# RESPi.net
KiCad netlist of a schematic drawn in EasyEDA Pro
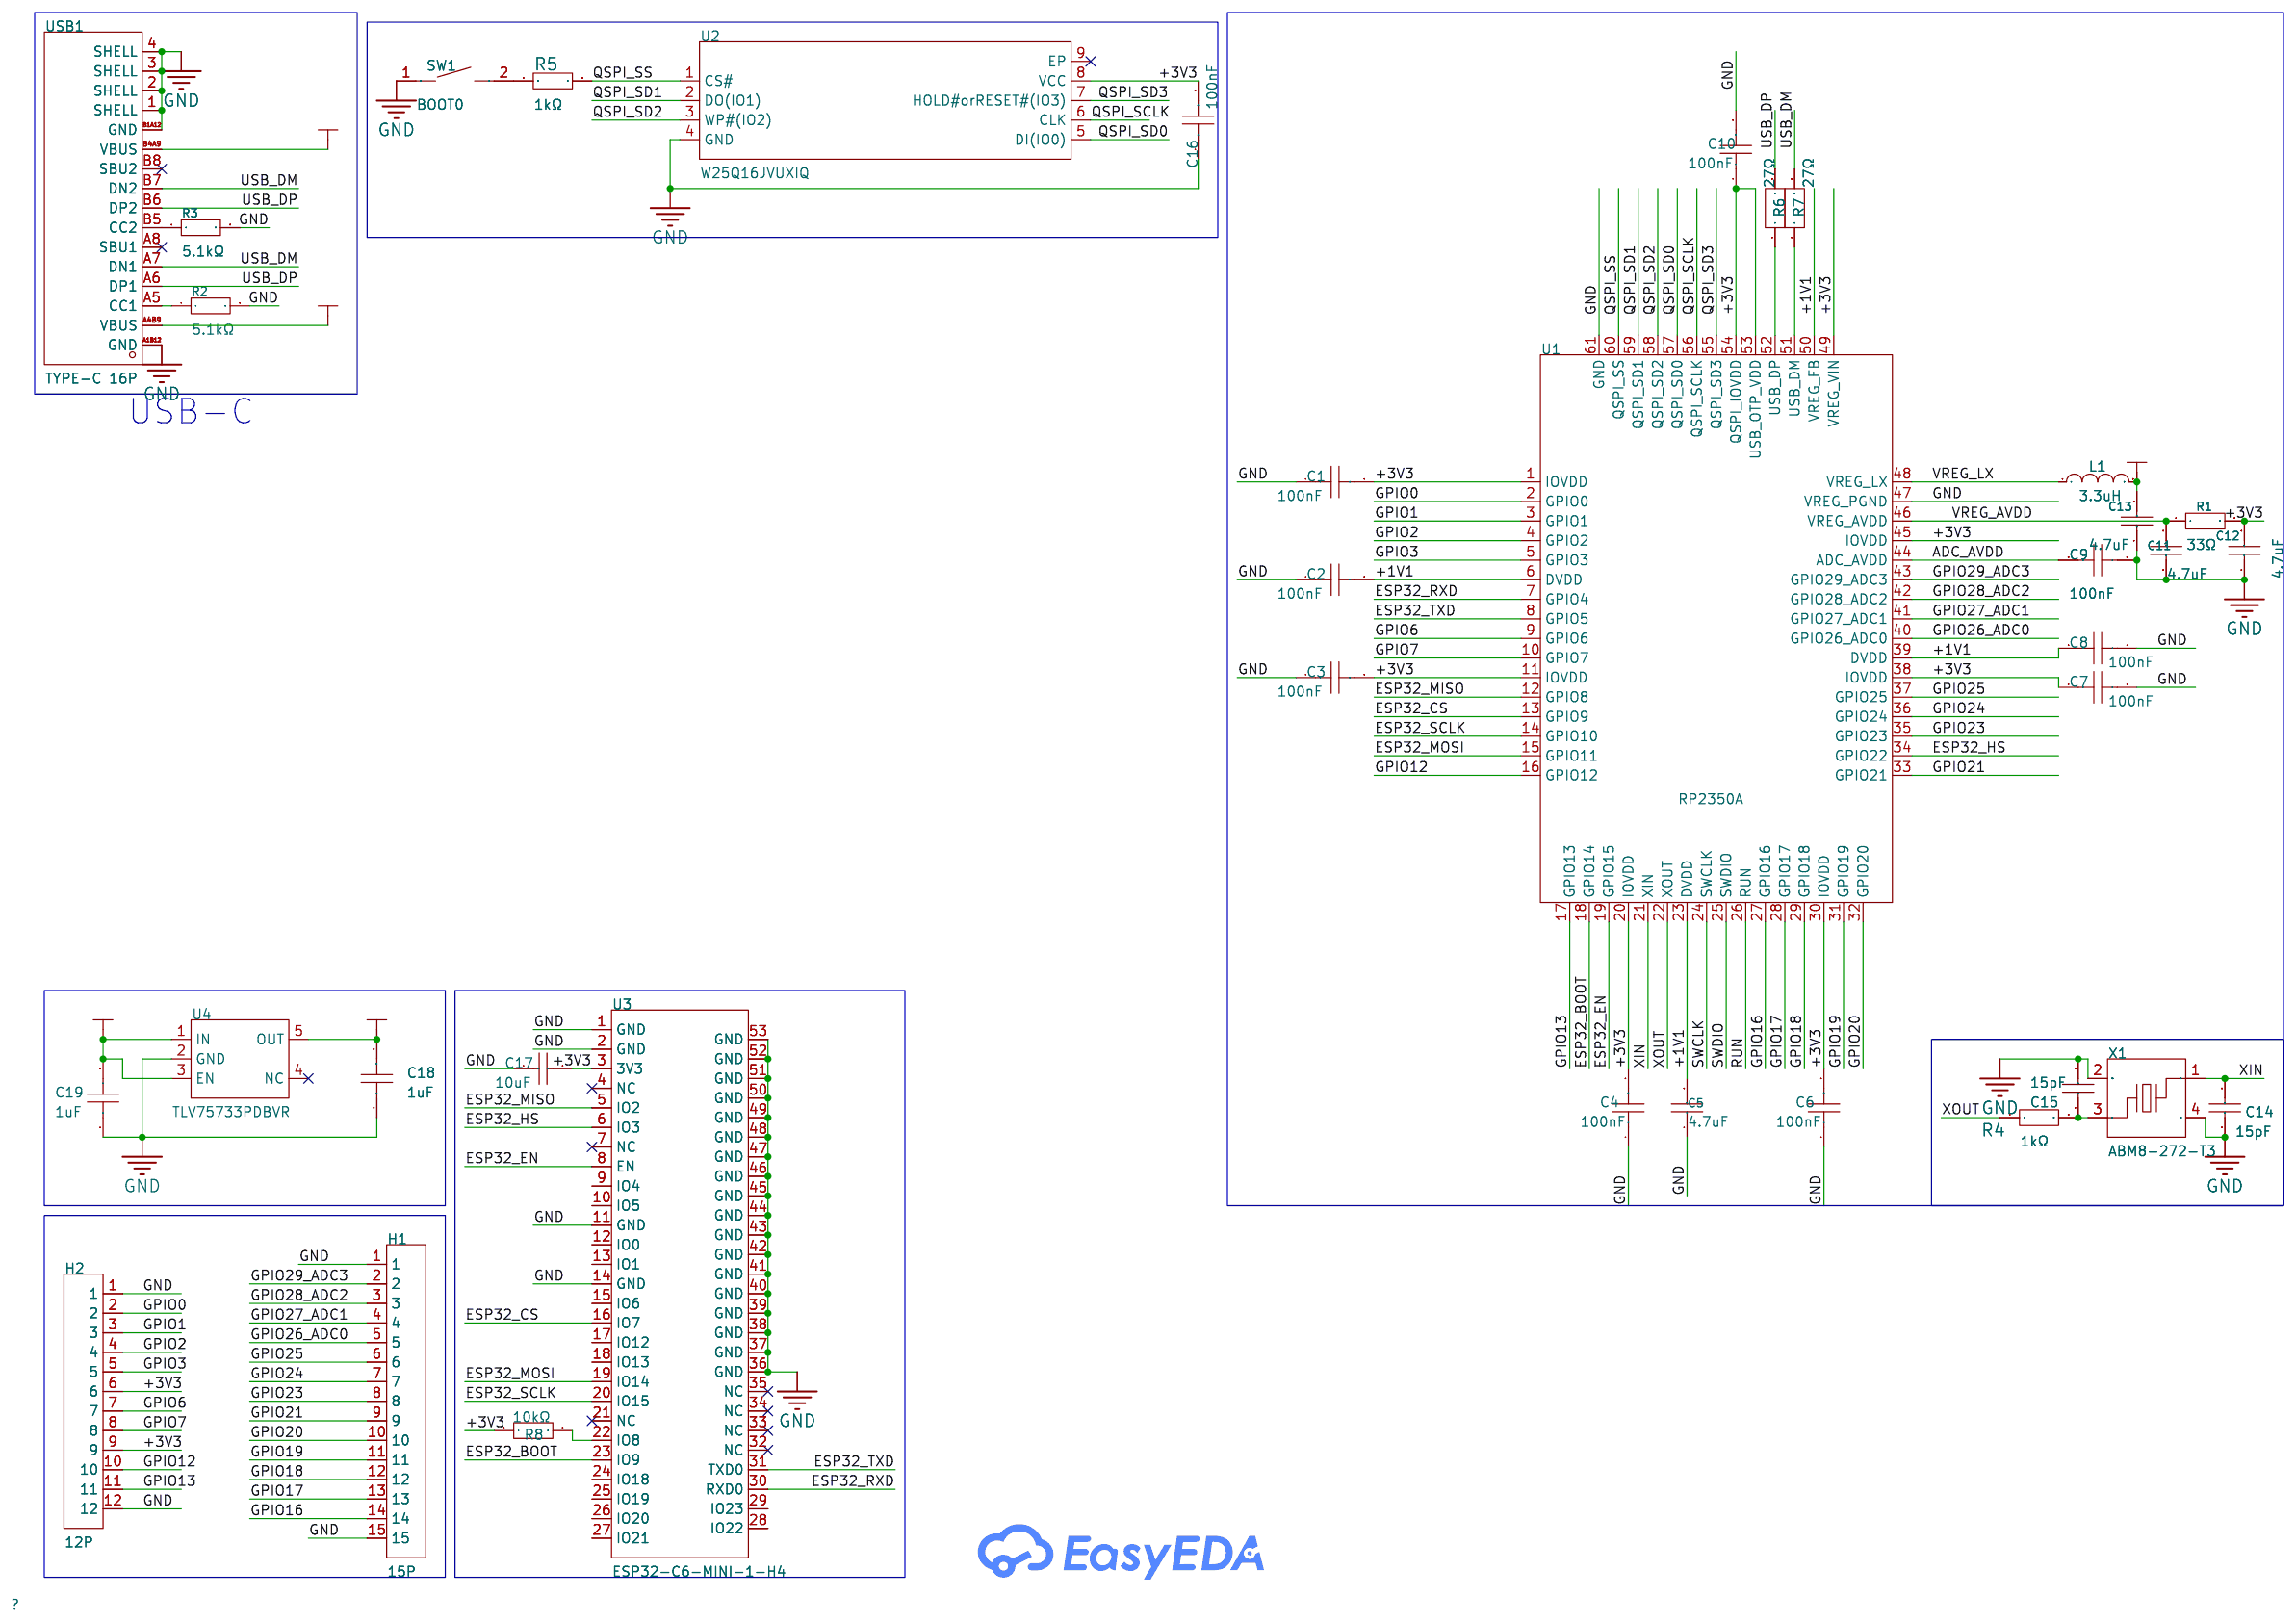
[diagram p0: schematic sheet]

(export (version "E")
  (design (tool "Eeschema 10.0.6"))
  (components
    (comp (ref "C1")
      (value "100nF")
      (footprint "easyedapro:C0402")
      (fields
        (field (name "Manufacturer Part") "CL05B104KO5NNNC")
        (field (name "Manufacturer") "SAMSUNG(三星)")
      )
      (libsource (lib "easyedapro") (part "CL05B104KO5NNNC"))
    )
    (comp (ref "C2")
      (value "100nF")
      (footprint "easyedapro:C0402")
      (fields
        (field (name "Manufacturer Part") "CL05B104KO5NNNC")
        (field (name "Manufacturer") "SAMSUNG(三星)")
      )
      (libsource (lib "easyedapro") (part "CL05B104KO5NNNC"))
    )
    (comp (ref "C3")
      (value "100nF")
      (footprint "easyedapro:C0402")
      (fields
        (field (name "Manufacturer Part") "CL05B104KO5NNNC")
        (field (name "Manufacturer") "SAMSUNG(三星)")
      )
      (libsource (lib "easyedapro") (part "CL05B104KO5NNNC"))
    )
    (comp (ref "C4")
      (value "100nF")
      (footprint "easyedapro:C0402")
      (fields
        (field (name "Manufacturer Part") "CL05B104KO5NNNC")
        (field (name "Manufacturer") "SAMSUNG(三星)")
      )
      (libsource (lib "easyedapro") (part "CL05B104KO5NNNC"))
    )
    (comp (ref "C5")
      (value "4.7uF")
      (footprint "easyedapro:C0402")
      (fields
        (field (name "Manufacturer Part") "CL05A475MP5NRNC")
        (field (name "Manufacturer") "SAMSUNG(三星)")
      )
      (libsource (lib "easyedapro") (part "CL05A475MP5NRNC"))
    )
    (comp (ref "C6")
      (value "100nF")
      (footprint "easyedapro:C0402")
      (fields
        (field (name "Manufacturer Part") "CL05B104KO5NNNC")
        (field (name "Manufacturer") "SAMSUNG(三星)")
      )
      (libsource (lib "easyedapro") (part "CL05B104KO5NNNC"))
    )
    (comp (ref "C7")
      (value "100nF")
      (footprint "easyedapro:C0402")
      (fields
        (field (name "Manufacturer Part") "CL05B104KO5NNNC")
        (field (name "Manufacturer") "SAMSUNG(三星)")
      )
      (libsource (lib "easyedapro") (part "CL05B104KO5NNNC"))
    )
    (comp (ref "C8")
      (value "100nF")
      (footprint "easyedapro:C0402")
      (fields
        (field (name "Manufacturer Part") "CL05B104KO5NNNC")
        (field (name "Manufacturer") "SAMSUNG(三星)")
      )
      (libsource (lib "easyedapro") (part "CL05B104KO5NNNC"))
    )
    (comp (ref "C9")
      (value "100nF")
      (footprint "easyedapro:C0402")
      (fields
        (field (name "Manufacturer Part") "CL05B104KO5NNNC")
        (field (name "Manufacturer") "SAMSUNG(三星)")
      )
      (libsource (lib "easyedapro") (part "CL05B104KO5NNNC"))
    )
    (comp (ref "C10")
      (value "100nF")
      (footprint "easyedapro:C0402")
      (fields
        (field (name "Manufacturer Part") "CL05B104KO5NNNC")
        (field (name "Manufacturer") "SAMSUNG(三星)")
      )
      (libsource (lib "easyedapro") (part "CL05B104KO5NNNC"))
    )
    (comp (ref "C11")
      (value "4.7uF")
      (footprint "easyedapro:C0402")
      (fields
        (field (name "Manufacturer Part") "CL05A475MP5NRNC")
        (field (name "Manufacturer") "SAMSUNG(三星)")
      )
      (libsource (lib "easyedapro") (part "CL05A475MP5NRNC"))
    )
    (comp (ref "C12")
      (value "4.7uF")
      (footprint "easyedapro:C0402")
      (fields
        (field (name "Manufacturer Part") "CL05A475MP5NRNC")
        (field (name "Manufacturer") "SAMSUNG(三星)")
      )
      (libsource (lib "easyedapro") (part "CL05A475MP5NRNC"))
    )
    (comp (ref "C13")
      (value "4.7uF")
      (footprint "easyedapro:C0402")
      (fields
        (field (name "Manufacturer Part") "CL05A475MP5NRNC")
        (field (name "Manufacturer") "SAMSUNG(三星)")
      )
      (libsource (lib "easyedapro") (part "CL05A475MP5NRNC"))
    )
    (comp (ref "C14")
      (value "15pF")
      (footprint "easyedapro:C0402")
      (fields (field (name "Manufacturer Part") "0402CG150J500NT") (field (name "Manufacturer") "FH(风华)"))
      (libsource (lib "easyedapro") (part "0402CG150J500NT"))
    )
    (comp (ref "C15")
      (value "15pF")
      (footprint "easyedapro:C0402")
      (fields (field (name "Manufacturer Part") "0402CG150J500NT") (field (name "Manufacturer") "FH(风华)"))
      (libsource (lib "easyedapro") (part "0402CG150J500NT"))
    )
    (comp (ref "C16")
      (value "100nF")
      (footprint "easyedapro:C0402")
      (fields
        (field (name "Manufacturer Part") "CL05B104KO5NNNC")
        (field (name "Manufacturer") "SAMSUNG(三星)")
      )
      (libsource (lib "easyedapro") (part "CL05B104KO5NNNC"))
    )
    (comp (ref "C17")
      (value "10uF")
      (footprint "easyedapro:C0402")
      (description "Capacitance:10uF Tolerance:±20% Tolerance:±20% Voltage Rating:6.3V Temperature Coefficient:X5R")
      (fields
        (field (name "Manufacturer Part") "CL05A106MQ5NUNC")
        (field (name "Manufacturer") "SAMSUNG(三星)")
      )
      (libsource (lib "easyedapro") (part "CL05A106MQ5NUNC"))
    )
    (comp (ref "C18")
      (value "1uF")
      (footprint "easyedapro:C0402")
      (description "Capacitance:1uF Tolerance:±10% Tolerance:±10% Voltage Rating:25V Temperature Coefficient:X5R")
      (fields
        (field (name "Manufacturer Part") "CL05A105KA5NQNC")
        (field (name "Manufacturer") "SAMSUNG(三星)")
      )
      (libsource (lib "easyedapro") (part "CL05A105KA5NQNC"))
    )
    (comp (ref "C19")
      (value "1uF")
      (footprint "easyedapro:C0402")
      (description "Capacitance:1uF Tolerance:±10% Tolerance:±10% Voltage Rating:25V Temperature Coefficient:X5R")
      (fields
        (field (name "Manufacturer Part") "CL05A105KA5NQNC")
        (field (name "Manufacturer") "SAMSUNG(三星)")
      )
      (libsource (lib "easyedapro") (part "CL05A105KA5NQNC"))
    )
    (comp (ref "H1")
      (value "15P")
      (footprint "easyedapro:HDR-TH_15P-P2.54-V-M")
      (fields (field (name "Manufacturer") "XKB Connection(中国星坤)"))
      (libsource (lib "easyedapro") (part "X6511WV-15H-C30D60"))
    )
    (comp (ref "H2")
      (value "12P")
      (footprint "easyedapro:HDR-TH_12P-P2.54-V-M")
      (fields (field (name "Manufacturer") "XKB Connection(中国星坤)"))
      (libsource (lib "easyedapro") (part "X6511WV-12H-C30D60"))
    )
    (comp (ref "L1")
      (value "3.3uH")
      (footprint "easyedapro:IND-SMD_L2.0-W1.6_AOTA-B201610S3R3-101-T")
      (fields (field (name "Manufacturer") "ABRACON"))
      (libsource (lib "easyedapro") (part "AOTA-B201610S3R3-101-T"))
    )
    (comp (ref "R1")
      (value "33Ω")
      (footprint "easyedapro:R0402")
      (fields
        (field (name "Manufacturer Part") "0402WGF330JTCE")
        (field (name "Manufacturer") "UNI-ROYAL(厚声)")
      )
      (libsource (lib "easyedapro") (part "0402WGF330JTCE"))
    )
    (comp (ref "R2")
      (value "5.1kΩ")
      (footprint "easyedapro:R0402")
      (fields
        (field (name "Manufacturer Part") "0402WGF5101TCE")
        (field (name "Manufacturer") "UNI-ROYAL(厚声)")
      )
      (libsource (lib "easyedapro") (part "0402WGF5101TCE"))
    )
    (comp (ref "R3")
      (value "5.1kΩ")
      (footprint "easyedapro:R0402")
      (fields
        (field (name "Manufacturer Part") "0402WGF5101TCE")
        (field (name "Manufacturer") "UNI-ROYAL(厚声)")
      )
      (libsource (lib "easyedapro") (part "0402WGF5101TCE"))
    )
    (comp (ref "R4")
      (value "1kΩ")
      (footprint "easyedapro:R0402")
      (fields
        (field (name "Manufacturer Part") "0402WGF1001TCE")
        (field (name "Manufacturer") "UNI-ROYAL(厚声)")
      )
      (libsource (lib "easyedapro") (part "0402WGF1001TCE"))
    )
    (comp (ref "R5")
      (value "1kΩ")
      (footprint "easyedapro:R0402")
      (fields
        (field (name "Manufacturer Part") "0402WGF1001TCE")
        (field (name "Manufacturer") "UNI-ROYAL(厚声)")
      )
      (libsource (lib "easyedapro") (part "0402WGF1001TCE"))
    )
    (comp (ref "R6")
      (value "27Ω")
      (footprint "easyedapro:R0402")
      (fields (field (name "Manufacturer Part") "WR04X270JTL") (field (name "Manufacturer") "Walsin(华新科)"))
      (libsource (lib "easyedapro") (part "WR04X270 JTL"))
    )
    (comp (ref "R7")
      (value "27Ω")
      (footprint "easyedapro:R0402")
      (fields (field (name "Manufacturer Part") "WR04X270JTL") (field (name "Manufacturer") "Walsin(华新科)"))
      (libsource (lib "easyedapro") (part "WR04X270 JTL"))
    )
    (comp (ref "R8")
      (value "10kΩ")
      (footprint "easyedapro:R0402")
      (fields
        (field (name "Manufacturer Part") "0402WGF1002TCE")
        (field (name "Manufacturer") "UNI-ROYAL(厚声)")
      )
      (libsource (lib "easyedapro") (part "0402WGF1002TCE"))
    )
    (comp (ref "SW1")
      (value "BOOT0")
      (footprint "easyedapro:SW-SMD_L3.9-W3.0-P4.45")
      (fields (field (name "Manufacturer") "XUNPU(讯普)"))
      (libsource (lib "easyedapro") (part "TS-1088-AR02016"))
    )
    (comp (ref "U1")
      (value "RP2350A")
      (footprint "easyedapro:QFN-60_L7.0-W7.0-P0.40-TL-EP3.4")
      (fields (field (name "Manufacturer") "Raspberry Pi(树莓派)"))
      (libsource (lib "easyedapro") (part "RP2350A_C42411118"))
    )
    (comp (ref "U2")
      (value "W25Q16JVUXIQ")
      (footprint "easyedapro:USON-8_L3.0-W2.0-P0.50-BL-EP")
      (fields (field (name "Manufacturer") "Winbond(华邦)"))
      (libsource (lib "easyedapro") (part "W25Q16JVUXIQ"))
    )
    (comp (ref "U3")
      (value "ESP32-C6-MINI-1-H4")
      (footprint "easyedapro:WIFIM-SMD_61P-L16.6-W13.2-P0.80-ESP32-C6-MINI-1-N4")
      (fields (field (name "Manufacturer") "ESPRESSIF(乐鑫)"))
      (libsource (lib "easyedapro") (part "ESP32-C6-MINI-1-H4"))
    )
    (comp (ref "U4")
      (value "TLV75733PDBVR")
      (footprint "easyedapro:SOT-23-5_L2.9-W1.6-P0.95-LS2.8-BL")
      (fields (field (name "Manufacturer") "TI(德州仪器)"))
      (libsource (lib "easyedapro") (part "TLV75733PDBVR"))
    )
    (comp (ref "USB1")
      (value "TYPE-C 16P")
      (footprint "easyedapro:USB-C-SMD_TYPE-C16PIN")
      (fields (field (name "Manufacturer") "SHOU HAN(首韩)"))
      (libsource (lib "easyedapro") (part "TYPE-C16PIN"))
    )
    (comp (ref "X1")
      (value "ABM8-272-T3")
      (footprint "easyedapro:CRYSTAL-SMD_4P-L3.2-W2.5-BL")
      (fields (field (name "Manufacturer") "ABRACON"))
      (libsource (lib "easyedapro") (part "ABM8-272-T3_C20625731"))
    )
  )
  (nets
    (net (code "1") (name "+1V1") (class "Default")
      (node (ref "C13") (pin "2") (pinfunction "2_2") (pintype "input"))
      (node (ref "C2") (pin "2") (pinfunction "2_2") (pintype "unspecified"))
      (node (ref "C5") (pin "2") (pinfunction "2_2") (pintype "input"))
      (node (ref "C8") (pin "2") (pinfunction "2_2") (pintype "unspecified"))
      (node (ref "L1") (pin "2") (pinfunction "2_2") (pintype "unspecified"))
      (node (ref "U1") (pin "23") (pinfunction "DVDD_23") (pintype "unspecified"))
      (node (ref "U1") (pin "39") (pinfunction "DVDD_39") (pintype "unspecified"))
      (node (ref "U1") (pin "50") (pinfunction "VREG_FB_50") (pintype "unspecified"))
      (node (ref "U1") (pin "6") (pinfunction "DVDD_6") (pintype "unspecified"))
    )
    (net (code "2") (name "+3V3") (class "Default")
      (node (ref "C1") (pin "2") (pinfunction "2_2") (pintype "unspecified"))
      (node (ref "C10") (pin "1") (pinfunction "1_1") (pintype "unspecified"))
      (node (ref "C12") (pin "2") (pinfunction "2_2") (pintype "input"))
      (node (ref "C16") (pin "2") (pinfunction "2_2") (pintype "unspecified"))
      (node (ref "C17") (pin "2") (pinfunction "2_2") (pintype "input"))
      (node (ref "C18") (pin "2") (pinfunction "2_2") (pintype "unspecified"))
      (node (ref "C3") (pin "2") (pinfunction "2_2") (pintype "unspecified"))
      (node (ref "C4") (pin "2") (pinfunction "2_2") (pintype "unspecified"))
      (node (ref "C6") (pin "2") (pinfunction "2_2") (pintype "unspecified"))
      (node (ref "C7") (pin "2") (pinfunction "2_2") (pintype "unspecified"))
      (node (ref "H2") (pin "6") (pinfunction "6_6") (pintype "unspecified"))
      (node (ref "H2") (pin "9") (pinfunction "9_9") (pintype "unspecified"))
      (node (ref "R1") (pin "2") (pinfunction "2_2") (pintype "input"))
      (node (ref "R8") (pin "1") (pinfunction "1_1") (pintype "input"))
      (node (ref "U1") (pin "1") (pinfunction "IOVDD_1") (pintype "unspecified"))
      (node (ref "U1") (pin "11") (pinfunction "IOVDD_11") (pintype "unspecified"))
      (node (ref "U1") (pin "20") (pinfunction "IOVDD_20") (pintype "unspecified"))
      (node (ref "U1") (pin "30") (pinfunction "IOVDD_30") (pintype "unspecified"))
      (node (ref "U1") (pin "38") (pinfunction "IOVDD_38") (pintype "unspecified"))
      (node (ref "U1") (pin "45") (pinfunction "IOVDD_45") (pintype "unspecified"))
      (node (ref "U1") (pin "49") (pinfunction "VREG_VIN_49") (pintype "unspecified"))
      (node (ref "U1") (pin "53") (pinfunction "USB_OTP_VDD_53") (pintype "unspecified"))
      (node (ref "U1") (pin "54") (pinfunction "QSPI_IOVDD_54") (pintype "unspecified"))
      (node (ref "U2") (pin "8") (pinfunction "VCC_8") (pintype "unspecified"))
      (node (ref "U3") (pin "3") (pinfunction "3V3_3") (pintype "unspecified"))
      (node (ref "U4") (pin "5") (pinfunction "OUT_5") (pintype "unspecified"))
    )
    (net (code "3") (name "/ADC_AVDD") (class "Default")
      (node (ref "C9") (pin "2") (pinfunction "2_2") (pintype "unspecified"))
      (node (ref "U1") (pin "44") (pinfunction "ADC_AVDD_44") (pintype "unspecified"))
    )
    (net (code "4") (name "/ESP32_BOOT") (class "Default")
      (node (ref "U1") (pin "18") (pinfunction "GPIO14_18") (pintype "unspecified"))
      (node (ref "U3") (pin "23") (pinfunction "IO9_23") (pintype "unspecified"))
    )
    (net (code "5") (name "/ESP32_CS") (class "Default")
      (node (ref "U1") (pin "13") (pinfunction "GPIO9_13") (pintype "unspecified"))
      (node (ref "U3") (pin "16") (pinfunction "IO7_16") (pintype "unspecified"))
    )
    (net (code "6") (name "/ESP32_EN") (class "Default")
      (node (ref "U1") (pin "19") (pinfunction "GPIO15_19") (pintype "unspecified"))
      (node (ref "U3") (pin "8") (pinfunction "EN_8") (pintype "unspecified"))
    )
    (net (code "7") (name "/ESP32_HS") (class "Default")
      (node (ref "U1") (pin "34") (pinfunction "GPIO22_34") (pintype "unspecified"))
      (node (ref "U3") (pin "6") (pinfunction "IO3_6") (pintype "unspecified"))
    )
    (net (code "8") (name "/ESP32_MISO") (class "Default")
      (node (ref "U1") (pin "12") (pinfunction "GPIO8_12") (pintype "unspecified"))
      (node (ref "U3") (pin "5") (pinfunction "IO2_5") (pintype "unspecified"))
    )
    (net (code "9") (name "/ESP32_MOSI") (class "Default")
      (node (ref "U1") (pin "15") (pinfunction "GPIO11_15") (pintype "unspecified"))
      (node (ref "U3") (pin "19") (pinfunction "IO14_19") (pintype "unspecified"))
    )
    (net (code "10") (name "/ESP32_RXD") (class "Default")
      (node (ref "U1") (pin "7") (pinfunction "GPIO4_7") (pintype "unspecified"))
      (node (ref "U3") (pin "30") (pinfunction "RXD0_30") (pintype "unspecified"))
    )
    (net (code "11") (name "/ESP32_SCLK") (class "Default")
      (node (ref "U1") (pin "14") (pinfunction "GPIO10_14") (pintype "unspecified"))
      (node (ref "U3") (pin "20") (pinfunction "IO15_20") (pintype "unspecified"))
    )
    (net (code "12") (name "/ESP32_TXD") (class "Default")
      (node (ref "U1") (pin "8") (pinfunction "GPIO5_8") (pintype "unspecified"))
      (node (ref "U3") (pin "31") (pinfunction "TXD0_31") (pintype "unspecified"))
    )
    (net (code "13") (name "/GPIO0") (class "Default")
      (node (ref "H2") (pin "2") (pinfunction "2_2") (pintype "unspecified"))
      (node (ref "U1") (pin "2") (pinfunction "GPIO0_2") (pintype "unspecified"))
    )
    (net (code "14") (name "/GPIO1") (class "Default")
      (node (ref "H2") (pin "3") (pinfunction "3_3") (pintype "unspecified"))
      (node (ref "U1") (pin "3") (pinfunction "GPIO1_3") (pintype "unspecified"))
    )
    (net (code "15") (name "/GPIO2") (class "Default")
      (node (ref "H2") (pin "4") (pinfunction "4_4") (pintype "unspecified"))
      (node (ref "U1") (pin "4") (pinfunction "GPIO2_4") (pintype "unspecified"))
    )
    (net (code "16") (name "/GPIO3") (class "Default")
      (node (ref "H2") (pin "5") (pinfunction "5_5") (pintype "unspecified"))
      (node (ref "U1") (pin "5") (pinfunction "GPIO3_5") (pintype "unspecified"))
    )
    (net (code "17") (name "/GPIO6") (class "Default")
      (node (ref "H2") (pin "7") (pinfunction "7_7") (pintype "unspecified"))
      (node (ref "U1") (pin "9") (pinfunction "GPIO6_9") (pintype "unspecified"))
    )
    (net (code "18") (name "/GPIO7") (class "Default")
      (node (ref "H2") (pin "8") (pinfunction "8_8") (pintype "unspecified"))
      (node (ref "U1") (pin "10") (pinfunction "GPIO7_10") (pintype "unspecified"))
    )
    (net (code "19") (name "/GPIO12") (class "Default")
      (node (ref "H2") (pin "10") (pinfunction "10_10") (pintype "unspecified"))
      (node (ref "U1") (pin "16") (pinfunction "GPIO12_16") (pintype "unspecified"))
    )
    (net (code "20") (name "/GPIO13") (class "Default")
      (node (ref "H2") (pin "11") (pinfunction "11_11") (pintype "unspecified"))
      (node (ref "U1") (pin "17") (pinfunction "GPIO13_17") (pintype "unspecified"))
    )
    (net (code "21") (name "/GPIO16") (class "Default")
      (node (ref "H1") (pin "14") (pinfunction "14_14") (pintype "unspecified"))
      (node (ref "U1") (pin "27") (pinfunction "GPIO16_27") (pintype "unspecified"))
    )
    (net (code "22") (name "/GPIO17") (class "Default")
      (node (ref "H1") (pin "13") (pinfunction "13_13") (pintype "unspecified"))
      (node (ref "U1") (pin "28") (pinfunction "GPIO17_28") (pintype "unspecified"))
    )
    (net (code "23") (name "/GPIO18") (class "Default")
      (node (ref "H1") (pin "12") (pinfunction "12_12") (pintype "unspecified"))
      (node (ref "U1") (pin "29") (pinfunction "GPIO18_29") (pintype "unspecified"))
    )
    (net (code "24") (name "/GPIO19") (class "Default")
      (node (ref "H1") (pin "11") (pinfunction "11_11") (pintype "unspecified"))
      (node (ref "U1") (pin "31") (pinfunction "GPIO19_31") (pintype "unspecified"))
    )
    (net (code "25") (name "/GPIO20") (class "Default")
      (node (ref "H1") (pin "10") (pinfunction "10_10") (pintype "unspecified"))
      (node (ref "U1") (pin "32") (pinfunction "GPIO20_32") (pintype "unspecified"))
    )
    (net (code "26") (name "/GPIO21") (class "Default")
      (node (ref "H1") (pin "9") (pinfunction "9_9") (pintype "unspecified"))
      (node (ref "U1") (pin "33") (pinfunction "GPIO21_33") (pintype "unspecified"))
    )
    (net (code "27") (name "/GPIO23") (class "Default")
      (node (ref "H1") (pin "8") (pinfunction "8_8") (pintype "unspecified"))
      (node (ref "U1") (pin "35") (pinfunction "GPIO23_35") (pintype "unspecified"))
    )
    (net (code "28") (name "/GPIO24") (class "Default")
      (node (ref "H1") (pin "7") (pinfunction "7_7") (pintype "unspecified"))
      (node (ref "U1") (pin "36") (pinfunction "GPIO24_36") (pintype "unspecified"))
    )
    (net (code "29") (name "/GPIO25") (class "Default")
      (node (ref "H1") (pin "6") (pinfunction "6_6") (pintype "unspecified"))
      (node (ref "U1") (pin "37") (pinfunction "GPIO25_37") (pintype "unspecified"))
    )
    (net (code "30") (name "/GPIO26_ADC0") (class "Default")
      (node (ref "H1") (pin "5") (pinfunction "5_5") (pintype "unspecified"))
      (node (ref "U1") (pin "40") (pinfunction "GPIO26_ADC0_40") (pintype "unspecified"))
    )
    (net (code "31") (name "/GPIO27_ADC1") (class "Default")
      (node (ref "H1") (pin "4") (pinfunction "4_4") (pintype "unspecified"))
      (node (ref "U1") (pin "41") (pinfunction "GPIO27_ADC1_41") (pintype "unspecified"))
    )
    (net (code "32") (name "/GPIO28_ADC2") (class "Default")
      (node (ref "H1") (pin "3") (pinfunction "3_3") (pintype "unspecified"))
      (node (ref "U1") (pin "42") (pinfunction "GPIO28_ADC2_42") (pintype "unspecified"))
    )
    (net (code "33") (name "/GPIO29_ADC3") (class "Default")
      (node (ref "H1") (pin "2") (pinfunction "2_2") (pintype "unspecified"))
      (node (ref "U1") (pin "43") (pinfunction "GPIO29_ADC3_43") (pintype "unspecified"))
    )
    (net (code "34") (name "/QSPI_SCLK") (class "Default")
      (node (ref "U1") (pin "56") (pinfunction "QSPI_SCLK_56") (pintype "unspecified"))
      (node (ref "U2") (pin "6") (pinfunction "CLK_6") (pintype "unspecified"))
    )
    (net (code "35") (name "/QSPI_SD0") (class "Default")
      (node (ref "U1") (pin "57") (pinfunction "QSPI_SD0_57") (pintype "unspecified"))
      (node (ref "U2") (pin "5") (pinfunction "DI(IO0)_5") (pintype "unspecified"))
    )
    (net (code "36") (name "/QSPI_SD1") (class "Default")
      (node (ref "U1") (pin "59") (pinfunction "QSPI_SD1_59") (pintype "unspecified"))
      (node (ref "U2") (pin "2") (pinfunction "DO(IO1)_2") (pintype "unspecified"))
    )
    (net (code "37") (name "/QSPI_SD2") (class "Default")
      (node (ref "U1") (pin "58") (pinfunction "QSPI_SD2_58") (pintype "unspecified"))
      (node (ref "U2") (pin "3") (pinfunction "WP#(IO2)_3") (pintype "unspecified"))
    )
    (net (code "38") (name "/QSPI_SD3") (class "Default")
      (node (ref "U1") (pin "55") (pinfunction "QSPI_SD3_55") (pintype "unspecified"))
      (node (ref "U2") (pin "7") (pinfunction "HOLD#orRESET#(IO3)_7") (pintype "unspecified"))
    )
    (net (code "39") (name "/QSPI_SS") (class "Default")
      (node (ref "R5") (pin "2") (pinfunction "2_2") (pintype "input"))
      (node (ref "U1") (pin "60") (pinfunction "QSPI_SS_60") (pintype "unspecified"))
      (node (ref "U2") (pin "1") (pinfunction "CS#_1") (pintype "unspecified"))
    )
    (net (code "40") (name "/RUN") (class "Default")
      (node (ref "U1") (pin "26") (pinfunction "RUN_26") (pintype "unspecified"))
    )
    (net (code "41") (name "/SWCLK") (class "Default")
      (node (ref "U1") (pin "24") (pinfunction "SWCLK_24") (pintype "unspecified"))
    )
    (net (code "42") (name "/SWDIO") (class "Default")
      (node (ref "U1") (pin "25") (pinfunction "SWDIO_25") (pintype "unspecified"))
    )
    (net (code "43") (name "/USB_DM") (class "Default")
      (node (ref "R7") (pin "2") (pinfunction "2_2") (pintype "unspecified"))
      (node (ref "USB1") (pin "A7") (pinfunction "DN1_A7") (pintype "unspecified"))
      (node (ref "USB1") (pin "B7") (pinfunction "DN2_B7") (pintype "unspecified"))
    )
    (net (code "44") (name "/USB_DP") (class "Default")
      (node (ref "R6") (pin "2") (pinfunction "2_2") (pintype "unspecified"))
      (node (ref "USB1") (pin "A6") (pinfunction "DP1_A6") (pintype "unspecified"))
      (node (ref "USB1") (pin "B6") (pinfunction "DP2_B6") (pintype "unspecified"))
    )
    (net (code "45") (name "/VREG_AVDD") (class "Default")
      (node (ref "C11") (pin "2") (pinfunction "2_2") (pintype "input"))
      (node (ref "R1") (pin "1") (pinfunction "1_1") (pintype "input"))
      (node (ref "U1") (pin "46") (pinfunction "VREG_AVDD_46") (pintype "unspecified"))
    )
    (net (code "46") (name "/VREG_LX") (class "Default")
      (node (ref "L1") (pin "1") (pinfunction "1_1") (pintype "unspecified"))
      (node (ref "U1") (pin "48") (pinfunction "VREG_LX_48") (pintype "unspecified"))
    )
    (net (code "47") (name "/XIN") (class "Default")
      (node (ref "C14") (pin "2") (pinfunction "2_2") (pintype "input"))
      (node (ref "U1") (pin "21") (pinfunction "XIN_21") (pintype "unspecified"))
      (node (ref "X1") (pin "1") (pinfunction "1_1") (pintype "input"))
    )
    (net (code "48") (name "/XOUT") (class "Default")
      (node (ref "R4") (pin "1") (pinfunction "1_1") (pintype "input"))
      (node (ref "U1") (pin "22") (pinfunction "XOUT_22") (pintype "unspecified"))
    )
    (net (code "49") (name "GND") (class "Default")
      (node (ref "C1") (pin "1") (pinfunction "1_1") (pintype "unspecified"))
      (node (ref "C10") (pin "2") (pinfunction "2_2") (pintype "unspecified"))
      (node (ref "C11") (pin "1") (pinfunction "1_1") (pintype "input"))
      (node (ref "C12") (pin "1") (pinfunction "1_1") (pintype "input"))
      (node (ref "C13") (pin "1") (pinfunction "1_1") (pintype "input"))
      (node (ref "C14") (pin "1") (pinfunction "1_1") (pintype "input"))
      (node (ref "C15") (pin "2") (pinfunction "2_2") (pintype "input"))
      (node (ref "C16") (pin "1") (pinfunction "1_1") (pintype "unspecified"))
      (node (ref "C17") (pin "1") (pinfunction "1_1") (pintype "input"))
      (node (ref "C18") (pin "1") (pinfunction "1_1") (pintype "unspecified"))
      (node (ref "C19") (pin "1") (pinfunction "1_1") (pintype "unspecified"))
      (node (ref "C2") (pin "1") (pinfunction "1_1") (pintype "unspecified"))
      (node (ref "C3") (pin "1") (pinfunction "1_1") (pintype "unspecified"))
      (node (ref "C4") (pin "1") (pinfunction "1_1") (pintype "unspecified"))
      (node (ref "C5") (pin "1") (pinfunction "1_1") (pintype "input"))
      (node (ref "C6") (pin "1") (pinfunction "1_1") (pintype "unspecified"))
      (node (ref "C7") (pin "1") (pinfunction "1_1") (pintype "unspecified"))
      (node (ref "C8") (pin "1") (pinfunction "1_1") (pintype "unspecified"))
      (node (ref "C9") (pin "1") (pinfunction "1_1") (pintype "unspecified"))
      (node (ref "H1") (pin "1") (pinfunction "1_1") (pintype "unspecified"))
      (node (ref "H1") (pin "15") (pinfunction "15_15") (pintype "unspecified"))
      (node (ref "H2") (pin "1") (pinfunction "1_1") (pintype "unspecified"))
      (node (ref "H2") (pin "12") (pinfunction "12_12") (pintype "unspecified"))
      (node (ref "R2") (pin "2") (pinfunction "2_2") (pintype "input"))
      (node (ref "R3") (pin "2") (pinfunction "2_2") (pintype "input"))
      (node (ref "SW1") (pin "1") (pinfunction "1_1") (pintype "unspecified"))
      (node (ref "U1") (pin "47") (pinfunction "VREG_PGND_47") (pintype "unspecified"))
      (node (ref "U1") (pin "61") (pinfunction "GND_61") (pintype "unspecified"))
      (node (ref "U2") (pin "4") (pinfunction "GND_4") (pintype "unspecified"))
      (node (ref "U3") (pin "1") (pinfunction "GND_1") (pintype "unspecified"))
      (node (ref "U3") (pin "11") (pinfunction "GND_11") (pintype "unspecified"))
      (node (ref "U3") (pin "14") (pinfunction "GND_14") (pintype "unspecified"))
      (node (ref "U3") (pin "2") (pinfunction "GND_2") (pintype "unspecified"))
      (node (ref "U3") (pin "36") (pinfunction "GND_36") (pintype "unspecified"))
      (node (ref "U3") (pin "37") (pinfunction "GND_37") (pintype "unspecified"))
      (node (ref "U3") (pin "38") (pinfunction "GND_38") (pintype "unspecified"))
      (node (ref "U3") (pin "39") (pinfunction "GND_39") (pintype "unspecified"))
      (node (ref "U3") (pin "40") (pinfunction "GND_40") (pintype "unspecified"))
      (node (ref "U3") (pin "41") (pinfunction "GND_41") (pintype "unspecified"))
      (node (ref "U3") (pin "42") (pinfunction "GND_42") (pintype "unspecified"))
      (node (ref "U3") (pin "43") (pinfunction "GND_43") (pintype "unspecified"))
      (node (ref "U3") (pin "44") (pinfunction "GND_44") (pintype "unspecified"))
      (node (ref "U3") (pin "45") (pinfunction "GND_45") (pintype "unspecified"))
      (node (ref "U3") (pin "46") (pinfunction "GND_46") (pintype "unspecified"))
      (node (ref "U3") (pin "47") (pinfunction "GND_47") (pintype "unspecified"))
      (node (ref "U3") (pin "48") (pinfunction "GND_48") (pintype "unspecified"))
      (node (ref "U3") (pin "49") (pinfunction "GND_49") (pintype "unspecified"))
      (node (ref "U3") (pin "50") (pinfunction "GND_50") (pintype "unspecified"))
      (node (ref "U3") (pin "51") (pinfunction "GND_51") (pintype "unspecified"))
      (node (ref "U3") (pin "52") (pinfunction "GND_52") (pintype "unspecified"))
      (node (ref "U3") (pin "53") (pinfunction "GND_53") (pintype "unspecified"))
      (node (ref "U4") (pin "2") (pinfunction "GND_2") (pintype "unspecified"))
      (node (ref "USB1") (pin "1") (pinfunction "SHELL_1") (pintype "unspecified"))
      (node (ref "USB1") (pin "2") (pinfunction "SHELL_2") (pintype "unspecified"))
      (node (ref "USB1") (pin "3") (pinfunction "SHELL_3") (pintype "unspecified"))
      (node (ref "USB1") (pin "4") (pinfunction "SHELL_4") (pintype "unspecified"))
      (node (ref "USB1") (pin "A1B12") (pinfunction "GND_A1B12") (pintype "unspecified"))
      (node (ref "USB1") (pin "B1A12") (pinfunction "GND_B1A12") (pintype "unspecified"))
      (node (ref "X1") (pin "2") (pinfunction "GND_2") (pintype "input"))
      (node (ref "X1") (pin "4") (pinfunction "GND_4") (pintype "input"))
    )
    (net (code "50") (name "Net-(C15-Pad1)") (class "Default")
      (node (ref "C15") (pin "1") (pinfunction "1_1") (pintype "input"))
      (node (ref "R4") (pin "2") (pinfunction "2_2") (pintype "input"))
      (node (ref "X1") (pin "3") (pinfunction "3_3") (pintype "input"))
    )
    (net (code "51") (name "Net-(R5-Pad1)") (class "Default")
      (node (ref "R5") (pin "1") (pinfunction "1_1") (pintype "input"))
      (node (ref "SW1") (pin "2") (pinfunction "2_2") (pintype "unspecified"))
    )
    (net (code "52") (name "Net-(U1-USB_DM)") (class "Default")
      (node (ref "R7") (pin "1") (pinfunction "1_1") (pintype "unspecified"))
      (node (ref "U1") (pin "51") (pinfunction "USB_DM_51") (pintype "unspecified"))
    )
    (net (code "53") (name "Net-(U1-USB_DP)") (class "Default")
      (node (ref "R6") (pin "1") (pinfunction "1_1") (pintype "unspecified"))
      (node (ref "U1") (pin "52") (pinfunction "USB_DP_52") (pintype "unspecified"))
    )
    (net (code "54") (name "Net-(U3-IO8)") (class "Default")
      (node (ref "R8") (pin "2") (pinfunction "2_2") (pintype "input"))
      (node (ref "U3") (pin "22") (pinfunction "IO8_22") (pintype "unspecified"))
    )
    (net (code "55") (name "Net-(USB1-CC1)") (class "Default")
      (node (ref "R2") (pin "1") (pinfunction "1_1") (pintype "input"))
      (node (ref "USB1") (pin "A5") (pinfunction "CC1_A5") (pintype "unspecified"))
    )
    (net (code "56") (name "Net-(USB1-CC2)") (class "Default")
      (node (ref "R3") (pin "1") (pinfunction "1_1") (pintype "input"))
      (node (ref "USB1") (pin "B5") (pinfunction "CC2_B5") (pintype "unspecified"))
    )
    (net (code "57") (name "VBUS") (class "Default")
      (node (ref "C19") (pin "2") (pinfunction "2_2") (pintype "unspecified"))
      (node (ref "U4") (pin "1") (pinfunction "IN_1") (pintype "unspecified"))
      (node (ref "U4") (pin "3") (pinfunction "EN_3") (pintype "unspecified"))
      (node (ref "USB1") (pin "A4B9") (pinfunction "VBUS_A4B9") (pintype "unspecified"))
      (node (ref "USB1") (pin "B4A9") (pinfunction "VBUS_B4A9") (pintype "unspecified"))
    )
    (net (code "58") (name "unconnected-(U2-EP-Pad9)") (class "Default")
      (node (ref "U2") (pin "9") (pinfunction "EP_9") (pintype "unspecified+no_connect"))
    )
    (net (code "59") (name "unconnected-(U3-IO0-Pad12)") (class "Default")
      (node (ref "U3") (pin "12") (pinfunction "IO0_12") (pintype "unspecified"))
    )
    (net (code "60") (name "unconnected-(U3-IO1-Pad13)") (class "Default")
      (node (ref "U3") (pin "13") (pinfunction "IO1_13") (pintype "unspecified"))
    )
    (net (code "61") (name "unconnected-(U3-IO4-Pad9)") (class "Default")
      (node (ref "U3") (pin "9") (pinfunction "IO4_9") (pintype "unspecified"))
    )
    (net (code "62") (name "unconnected-(U3-IO5-Pad10)") (class "Default")
      (node (ref "U3") (pin "10") (pinfunction "IO5_10") (pintype "unspecified"))
    )
    (net (code "63") (name "unconnected-(U3-IO6-Pad15)") (class "Default")
      (node (ref "U3") (pin "15") (pinfunction "IO6_15") (pintype "unspecified"))
    )
    (net (code "64") (name "unconnected-(U3-IO12-Pad17)") (class "Default")
      (node (ref "U3") (pin "17") (pinfunction "IO12_17") (pintype "unspecified"))
    )
    (net (code "65") (name "unconnected-(U3-IO13-Pad18)") (class "Default")
      (node (ref "U3") (pin "18") (pinfunction "IO13_18") (pintype "unspecified"))
    )
    (net (code "66") (name "unconnected-(U3-IO18-Pad24)") (class "Default")
      (node (ref "U3") (pin "24") (pinfunction "IO18_24") (pintype "unspecified"))
    )
    (net (code "67") (name "unconnected-(U3-IO19-Pad25)") (class "Default")
      (node (ref "U3") (pin "25") (pinfunction "IO19_25") (pintype "unspecified"))
    )
    (net (code "68") (name "unconnected-(U3-IO20-Pad26)") (class "Default")
      (node (ref "U3") (pin "26") (pinfunction "IO20_26") (pintype "unspecified"))
    )
    (net (code "69") (name "unconnected-(U3-IO21-Pad27)") (class "Default")
      (node (ref "U3") (pin "27") (pinfunction "IO21_27") (pintype "unspecified"))
    )
    (net (code "70") (name "unconnected-(U3-IO22-Pad28)") (class "Default")
      (node (ref "U3") (pin "28") (pinfunction "IO22_28") (pintype "unspecified"))
    )
    (net (code "71") (name "unconnected-(U3-IO23-Pad29)") (class "Default")
      (node (ref "U3") (pin "29") (pinfunction "IO23_29") (pintype "unspecified"))
    )
    (net (code "72") (name "unconnected-(U3-NC-Pad4)") (class "Default")
      (node (ref "U3") (pin "4") (pinfunction "NC_4") (pintype "unspecified+no_connect"))
    )
    (net (code "73") (name "unconnected-(U3-NC-Pad7)") (class "Default")
      (node (ref "U3") (pin "7") (pinfunction "NC_7") (pintype "unspecified+no_connect"))
    )
    (net (code "74") (name "unconnected-(U3-NC-Pad21)") (class "Default")
      (node (ref "U3") (pin "21") (pinfunction "NC_21") (pintype "unspecified+no_connect"))
    )
    (net (code "75") (name "unconnected-(U3-NC-Pad32)") (class "Default")
      (node (ref "U3") (pin "32") (pinfunction "NC_32") (pintype "unspecified+no_connect"))
    )
    (net (code "76") (name "unconnected-(U3-NC-Pad33)") (class "Default")
      (node (ref "U3") (pin "33") (pinfunction "NC_33") (pintype "unspecified+no_connect"))
    )
    (net (code "77") (name "unconnected-(U3-NC-Pad34)") (class "Default")
      (node (ref "U3") (pin "34") (pinfunction "NC_34") (pintype "unspecified+no_connect"))
    )
    (net (code "78") (name "unconnected-(U3-NC-Pad35)") (class "Default")
      (node (ref "U3") (pin "35") (pinfunction "NC_35") (pintype "unspecified+no_connect"))
    )
    (net (code "79") (name "unconnected-(U4-NC-Pad4)") (class "Default")
      (node (ref "U4") (pin "4") (pinfunction "NC_4") (pintype "unspecified+no_connect"))
    )
    (net (code "80") (name "unconnected-(USB1-SBU1-PadA8)") (class "Default")
      (node (ref "USB1") (pin "A8") (pinfunction "SBU1_A8") (pintype "unspecified+no_connect"))
    )
    (net (code "81") (name "unconnected-(USB1-SBU2-PadB8)") (class "Default")
      (node (ref "USB1") (pin "B8") (pinfunction "SBU2_B8") (pintype "unspecified+no_connect"))
    )
  )
)
